# Fri3D_2020_03.net
KiCad netlist of a schematic drawn in Altium Designer
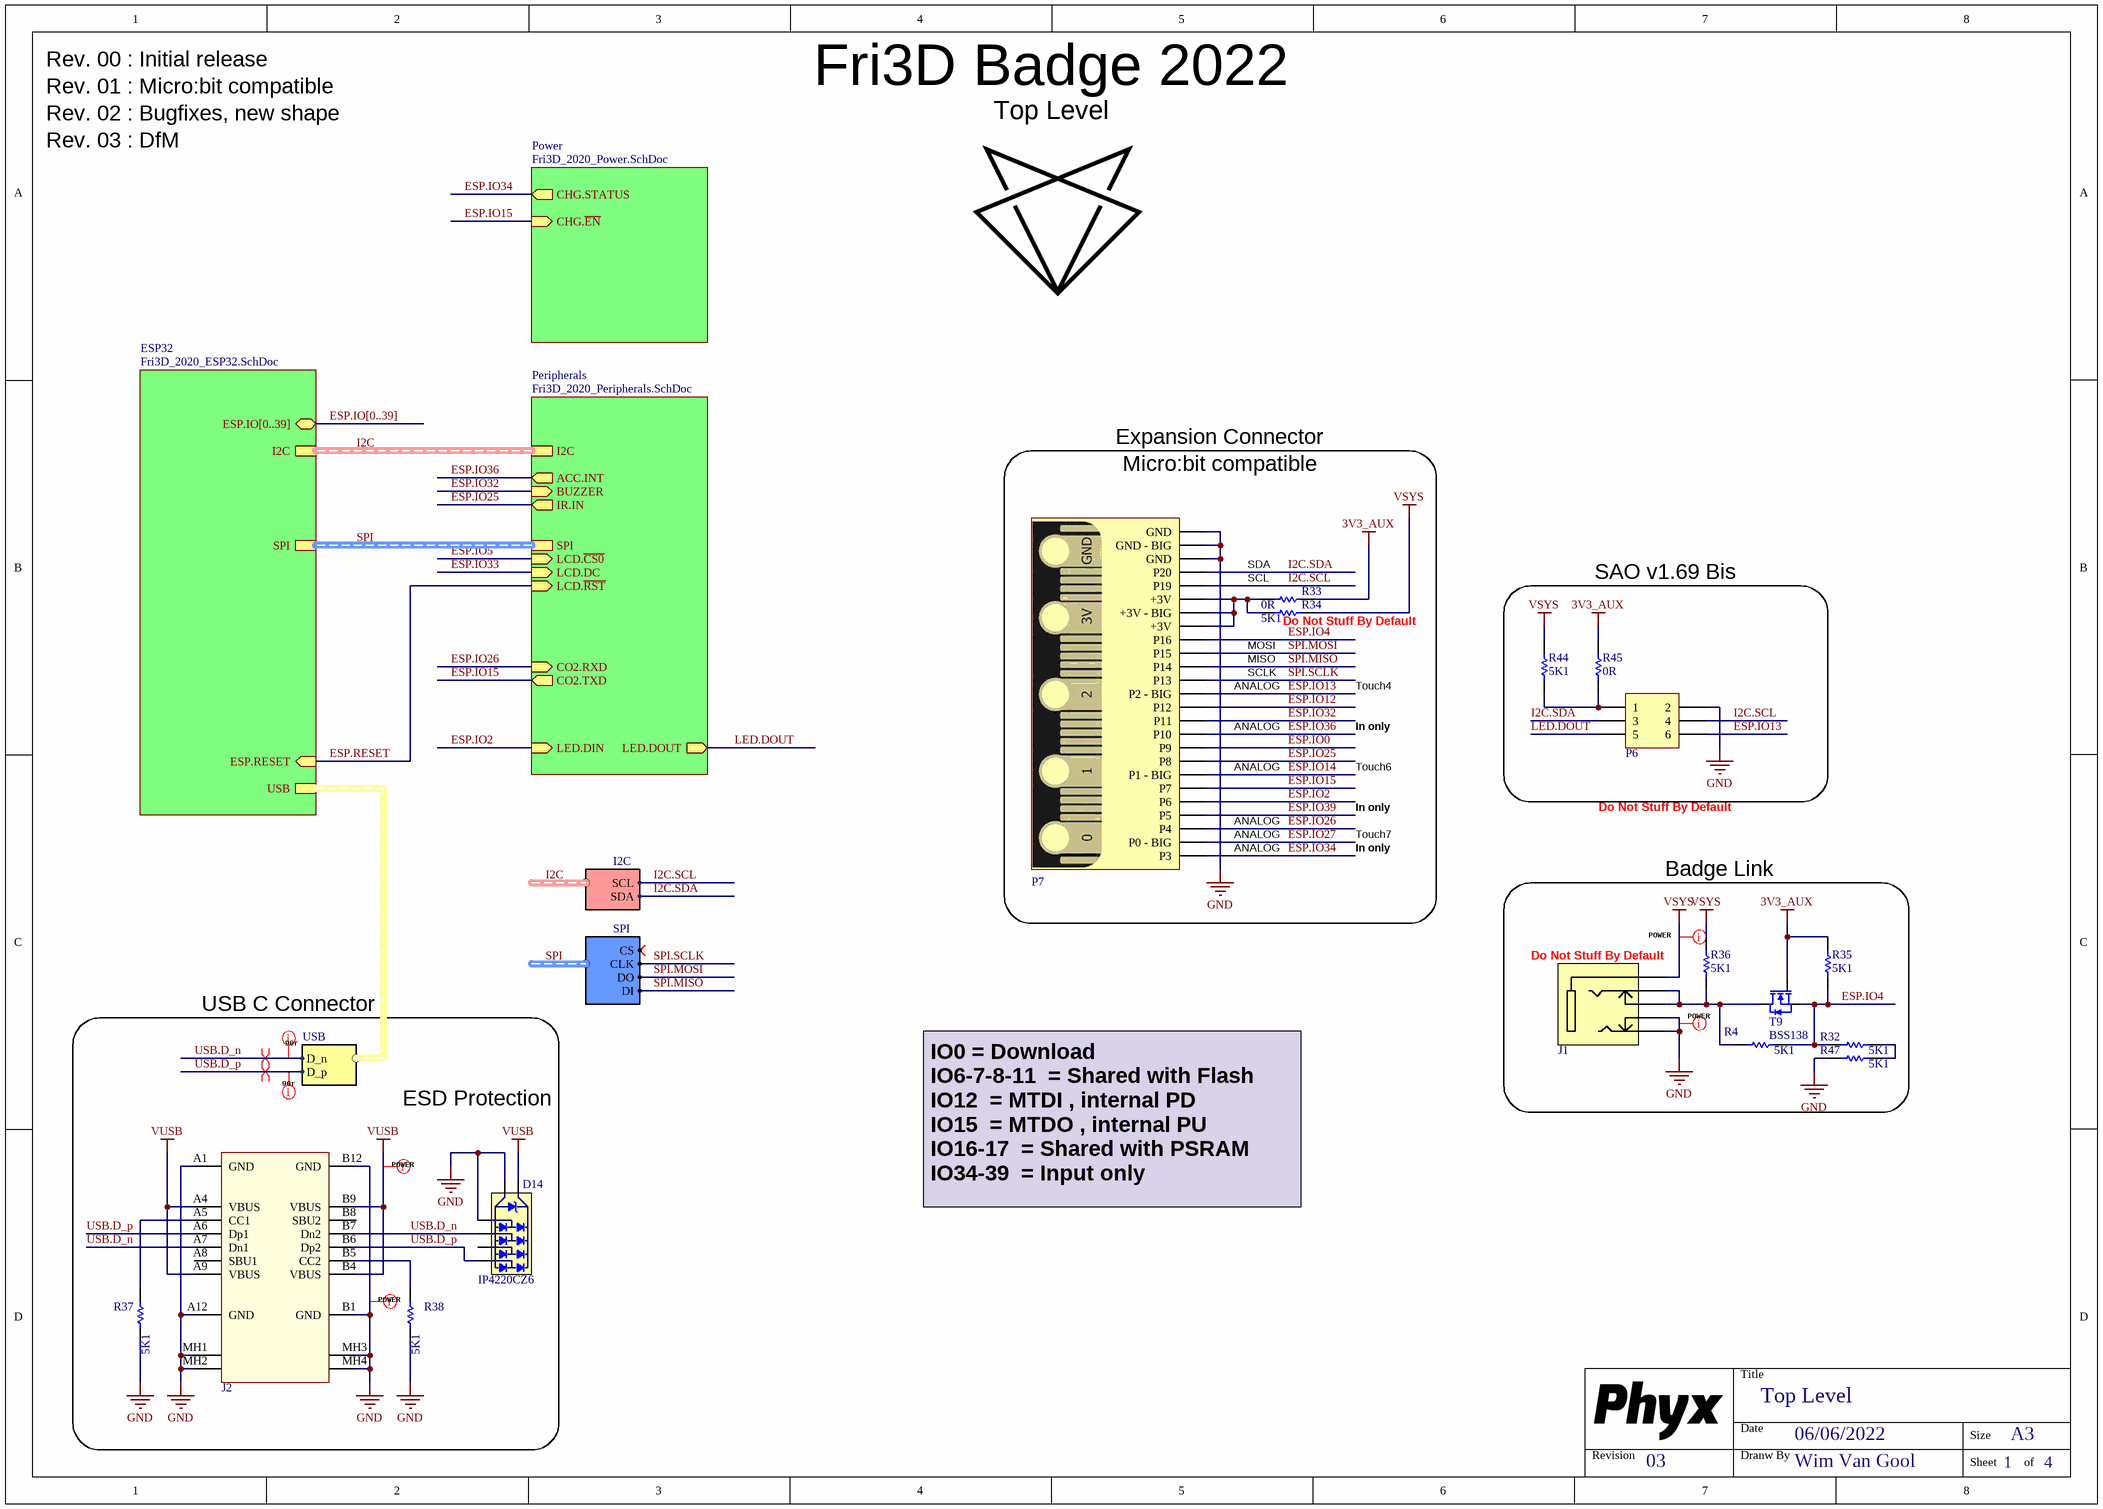
[diagram p0: Fri3D_2020_03.SchDoc]

(export (version "E")
  (design (tool "Eeschema 10.0.6"))
  (components
    (comp (ref "D14")
      (value "IP4220CZ6")
      (footprint "NXP_SOT457")
      (description "=Description")
      (fields (field (name "Comment") "TVS Diode Dual USB"))
      (libsource (lib "Phyx_Components") (part "NXP_IP4220CZ6"))
    )
    (comp (ref "J1")
      (value "3.5mm jack, dual switch, black, 3 contacts")
      (footprint "CUI_SJ1-3525NG")
      (description "=Description")
      (libsource (lib "Phyx_Components") (part "CUI_SJ1-3525NG"))
    )
    (comp (ref "J2")
      (value "USB 2.0 C Reversible Receptacle Horizontal")
      (footprint "HRO_TYPE-C-31-M-12")
      (libsource (lib "Phyx_Components") (part "USB_C_16_4"))
    )
    (comp (ref "P6")
      (value "Receptacle 3x2")
      (footprint "RCPT2X3")
      (libsource (lib "Phyx_Components") (part "Header 3X2"))
    )
    (comp (ref "P7")
      (value "MicroBit PCB connector")
      (footprint "MicroBIT_V2_PCB")
      (libsource (lib "Phyx_Components") (part "Header 25_MicroBit"))
    )
    (comp (ref "R4")
      (value "5K1")
      (footprint "R0603_N")
      (fields (field (name "Comment") "RESISTOR"))
      (libsource (lib "Phyx_Components") (part "RESISTOR"))
    )
    (comp (ref "R32")
      (value "5K1")
      (footprint "R0603_N")
      (fields (field (name "Comment") "RESISTOR"))
      (libsource (lib "Phyx_Components") (part "RESISTOR"))
    )
    (comp (ref "R33")
      (value "0R")
      (footprint "R0603_N")
      (fields (field (name "Comment") "RESISTOR"))
      (libsource (lib "Phyx_Components") (part "RESISTOR"))
    )
    (comp (ref "R34")
      (value "5K1")
      (footprint "R0603_N")
      (fields (field (name "Comment") "RESISTOR"))
      (libsource (lib "Phyx_Components") (part "RESISTOR"))
    )
    (comp (ref "R35")
      (value "5K1")
      (footprint "R0603_N")
      (fields (field (name "Comment") "RESISTOR"))
      (libsource (lib "Phyx_Components") (part "RESISTOR"))
    )
    (comp (ref "R36")
      (value "5K1")
      (footprint "R0603_N")
      (fields (field (name "Comment") "RESISTOR"))
      (libsource (lib "Phyx_Components") (part "RESISTOR"))
    )
    (comp (ref "R37")
      (value "5K1")
      (footprint "R0603_N")
      (fields (field (name "Comment") "RESISTOR"))
      (libsource (lib "Phyx_Components") (part "RESISTOR"))
    )
    (comp (ref "R38")
      (value "5K1")
      (footprint "R0603_N")
      (fields (field (name "Comment") "RESISTOR"))
      (libsource (lib "Phyx_Components") (part "RESISTOR"))
    )
    (comp (ref "R44")
      (value "5K1")
      (footprint "R0603_N")
      (fields (field (name "Comment") "RESISTOR"))
      (libsource (lib "Phyx_Components") (part "RESISTOR"))
    )
    (comp (ref "R45")
      (value "0R")
      (footprint "R0603_N")
      (fields (field (name "Comment") "RESISTOR"))
      (libsource (lib "Phyx_Components") (part "RESISTOR"))
    )
    (comp (ref "R47")
      (value "5K1")
      (footprint "R0603_N")
      (fields (field (name "Comment") "RESISTOR"))
      (libsource (lib "Phyx_Components") (part "RESISTOR"))
    )
    (comp (ref "T9")
      (value "BSS138")
      (footprint "SOT23-3")
      (fields (field (name "Comment") "0.2A N-Ch MOSFET Vgs 3.2"))
      (libsource (lib "Phyx_Components") (part "N_MOSFET_GSD"))
    )
  )
  (nets
    (net (code "31") (name "/ESP.IO0") (class "Default")
      (node (ref "P7") (pin "9") (pinfunction "P9_9") (pintype "passive"))
    )
    (net (code "32") (name "/ESP.IO2") (class "Default")
      (node (ref "P7") (pin "5") (pinfunction "P6_5") (pintype "passive"))
    )
    (net (code "33") (name "/ESP.IO4") (class "Default")
      (node (ref "P7") (pin "17") (pinfunction "P16_17") (pintype "passive"))
      (node (ref "R32") (pin "2") (pinfunction "2_2") (pintype "passive"))
      (node (ref "R35") (pin "2") (pinfunction "2_2") (pintype "passive"))
      (node (ref "R4") (pin "1") (pinfunction "1_1") (pintype "passive"))
      (node (ref "T9") (pin "2") (pinfunction "S_2") (pintype "passive"))
    )
    (net (code "35") (name "/ESP.IO12") (class "Default")
      (node (ref "P7") (pin "12") (pinfunction "P12_12") (pintype "passive"))
    )
    (net (code "36") (name "/ESP.IO13") (class "Default")
      (node (ref "P6") (pin "6") (pinfunction "6_6") (pintype "passive"))
      (node (ref "P7") (pin "13") (pinfunction "P2_-_BIG_13") (pintype "passive"))
    )
    (net (code "37") (name "/ESP.IO14") (class "Default")
      (node (ref "P7") (pin "7") (pinfunction "P1_-_BIG_7") (pintype "passive"))
    )
    (net (code "38") (name "/ESP.IO15") (class "Default")
      (node (ref "P7") (pin "6") (pinfunction "P7_6") (pintype "passive"))
    )
    (net (code "39") (name "/ESP.IO25") (class "Default")
      (node (ref "P7") (pin "8") (pinfunction "P8_8") (pintype "passive"))
    )
    (net (code "40") (name "/ESP.IO26") (class "Default")
      (node (ref "P7") (pin "3") (pinfunction "P4_3") (pintype "passive"))
    )
    (net (code "41") (name "/ESP.IO27") (class "Default")
      (node (ref "P7") (pin "2") (pinfunction "P0_-_BIG_2") (pintype "passive"))
    )
    (net (code "42") (name "/ESP.IO32") (class "Default")
      (node (ref "P7") (pin "11") (pinfunction "P11_11") (pintype "passive"))
    )
    (net (code "44") (name "/ESP.IO34") (class "Default")
      (node (ref "P7") (pin "1") (pinfunction "P3_1") (pintype "passive"))
    )
    (net (code "45") (name "/ESP.IO36") (class "Default")
      (node (ref "P7") (pin "10") (pinfunction "P10_10") (pintype "passive"))
    )
    (net (code "46") (name "/ESP.IO39") (class "Default")
      (node (ref "P7") (pin "4") (pinfunction "P5_4") (pintype "passive"))
    )
    (net (code "49") (name "/I2C.SCL") (class "Default")
      (node (ref "P6") (pin "4") (pinfunction "4_4") (pintype "passive"))
      (node (ref "P7") (pin "21") (pinfunction "P19_21") (pintype "passive"))
    )
    (net (code "50") (name "/I2C.SDA") (class "Default")
      (node (ref "P6") (pin "3") (pinfunction "3_3") (pintype "passive"))
      (node (ref "P7") (pin "22") (pinfunction "P20_22") (pintype "passive"))
    )
    (net (code "52") (name "/LED.DOUT") (class "Default")
      (node (ref "P6") (pin "5") (pinfunction "5_5") (pintype "passive"))
    )
    (net (code "53") (name "/SPI.MISO") (class "Default")
      (node (ref "P7") (pin "15") (pinfunction "P14_15") (pintype "passive"))
    )
    (net (code "54") (name "/SPI.MOSI") (class "Default")
      (node (ref "P7") (pin "16") (pinfunction "P15_16") (pintype "passive"))
    )
    (net (code "55") (name "/SPI.SCLK") (class "Default")
      (node (ref "P7") (pin "14") (pinfunction "P13_14") (pintype "passive"))
    )
    (net (code "57") (name "/USB.D_n") (class "Default")
      (node (ref "D14") (pin "1") (pinfunction "1_1") (pintype "passive"))
      (node (ref "J2") (pin "A7") (pinfunction "Dn1_A7") (pintype "passive"))
      (node (ref "J2") (pin "B7") (pinfunction "Dn2_B7") (pintype "passive"))
    )
    (net (code "58") (name "/USB.D_p") (class "Default")
      (node (ref "D14") (pin "6") (pinfunction "6_6") (pintype "passive"))
      (node (ref "J2") (pin "A6") (pinfunction "Dp1_A6") (pintype "passive"))
      (node (ref "J2") (pin "B6") (pinfunction "Dp2_B6") (pintype "passive"))
    )
    (net (code "62") (name "3V3_AUX") (class "Default")
      (node (ref "R33") (pin "1") (pinfunction "1_1") (pintype "passive"))
      (node (ref "R35") (pin "1") (pinfunction "1_1") (pintype "passive"))
      (node (ref "R45") (pin "1") (pinfunction "1_1") (pintype "passive"))
      (node (ref "T9") (pin "1") (pinfunction "G_1") (pintype "passive"))
    )
    (net (code "63") (name "GND") (class "Default")
      (node (ref "D14") (pin "2") (pinfunction "GND_2") (pintype "passive"))
      (node (ref "D14") (pin "3") (pinfunction "3_3") (pintype "passive"))
      (node (ref "J1") (pin "2") (pinfunction "Tip_2") (pintype "passive"))
      (node (ref "J1") (pin "4") (pinfunction "4_4") (pintype "passive"))
      (node (ref "J2") (pin "A1") (pinfunction "GND_A1") (pintype "passive"))
      (node (ref "J2") (pin "A12") (pinfunction "GND_A12") (pintype "passive"))
      (node (ref "J2") (pin "B1") (pinfunction "GND_B1") (pintype "passive"))
      (node (ref "J2") (pin "B12") (pinfunction "GND_B12") (pintype "passive"))
      (node (ref "J2") (pin "MH1") (pinfunction "Tab_MH1") (pintype "passive"))
      (node (ref "J2") (pin "MH2") (pinfunction "Tab_MH2") (pintype "passive"))
      (node (ref "J2") (pin "MH3") (pinfunction "Tab_MH3") (pintype "passive"))
      (node (ref "J2") (pin "MH4") (pinfunction "Tab_MH4") (pintype "passive"))
      (node (ref "P6") (pin "2") (pinfunction "2_2") (pintype "passive"))
      (node (ref "P7") (pin "23") (pinfunction "GND_23") (pintype "passive"))
      (node (ref "P7") (pin "24") (pinfunction "GND_-_BIG_24") (pintype "passive"))
      (node (ref "P7") (pin "25") (pinfunction "GND_25") (pintype "passive"))
      (node (ref "R37") (pin "2") (pinfunction "2_2") (pintype "passive"))
      (node (ref "R38") (pin "2") (pinfunction "2_2") (pintype "passive"))
      (node (ref "R47") (pin "2") (pinfunction "2_2") (pintype "passive"))
    )
    (net (code "64") (name "Net-(J1-Ring)") (class "Default")
      (node (ref "J1") (pin "3") (pinfunction "Ring_3") (pintype "passive"))
      (node (ref "J1") (pin "5") (pinfunction "5_5") (pintype "passive"))
      (node (ref "R36") (pin "2") (pinfunction "2_2") (pintype "passive"))
      (node (ref "R4") (pin "2") (pinfunction "2_2") (pintype "passive"))
      (node (ref "T9") (pin "3") (pinfunction "D_3") (pintype "passive"))
    )
    (net (code "65") (name "Net-(J2-CC1)") (class "Default")
      (node (ref "J2") (pin "A5") (pinfunction "CC1_A5") (pintype "passive"))
      (node (ref "R37") (pin "1") (pinfunction "1_1") (pintype "passive"))
    )
    (net (code "66") (name "Net-(J2-CC2)") (class "Default")
      (node (ref "J2") (pin "B5") (pinfunction "CC2_B5") (pintype "passive"))
      (node (ref "R38") (pin "1") (pinfunction "1_1") (pintype "passive"))
    )
    (net (code "67") (name "Net-(P6-Pad1)") (class "Default")
      (node (ref "P6") (pin "1") (pinfunction "1_1") (pintype "passive"))
      (node (ref "R44") (pin "1") (pinfunction "1_1") (pintype "passive"))
      (node (ref "R45") (pin "2") (pinfunction "2_2") (pintype "passive"))
    )
    (net (code "68") (name "Net-(P7-+3V_-_BIG)") (class "Default")
      (node (ref "P7") (pin "18") (pinfunction "+3V_18") (pintype "passive"))
      (node (ref "P7") (pin "19") (pinfunction "+3V_-_BIG_19") (pintype "passive"))
      (node (ref "P7") (pin "20") (pinfunction "+3V_20") (pintype "passive"))
      (node (ref "R33") (pin "2") (pinfunction "2_2") (pintype "passive"))
      (node (ref "R34") (pin "1") (pinfunction "1_1") (pintype "passive"))
    )
    (net (code "69") (name "Net-(R32-Pad1)") (class "Default")
      (node (ref "R32") (pin "1") (pinfunction "1_1") (pintype "passive"))
      (node (ref "R47") (pin "1") (pinfunction "1_1") (pintype "passive"))
    )
    (net (code "70") (name "VSYS") (class "Default")
      (node (ref "J1") (pin "1") (pinfunction "Sleeve_1") (pintype "passive"))
      (node (ref "R34") (pin "2") (pinfunction "2_2") (pintype "passive"))
      (node (ref "R36") (pin "1") (pinfunction "1_1") (pintype "passive"))
      (node (ref "R44") (pin "2") (pinfunction "2_2") (pintype "passive"))
    )
    (net (code "71") (name "VUSB") (class "Default")
      (node (ref "D14") (pin "5") (pinfunction "VBus_5") (pintype "passive"))
      (node (ref "J2") (pin "A4") (pinfunction "VBUS_A4") (pintype "passive"))
      (node (ref "J2") (pin "A9") (pinfunction "VBUS_A9") (pintype "passive"))
      (node (ref "J2") (pin "B4") (pinfunction "VBUS_B4") (pintype "passive"))
      (node (ref "J2") (pin "B9") (pinfunction "VBUS_B9") (pintype "passive"))
    )
    (net (code "72") (name "unconnected-(D14-Pad4)") (class "Default")
      (node (ref "D14") (pin "4") (pinfunction "4_4") (pintype "passive"))
    )
    (net (code "73") (name "unconnected-(J2-SBU1-PadA8)") (class "Default")
      (node (ref "J2") (pin "A8") (pinfunction "SBU1_A8") (pintype "passive"))
    )
    (net (code "74") (name "unconnected-(J2-SBU2-PadB8)") (class "Default")
      (node (ref "J2") (pin "B8") (pinfunction "SBU2_B8") (pintype "passive"))
    )
  )
)
